# punto5sq.net
KiCad netlist of a schematic drawn in Altium Designer
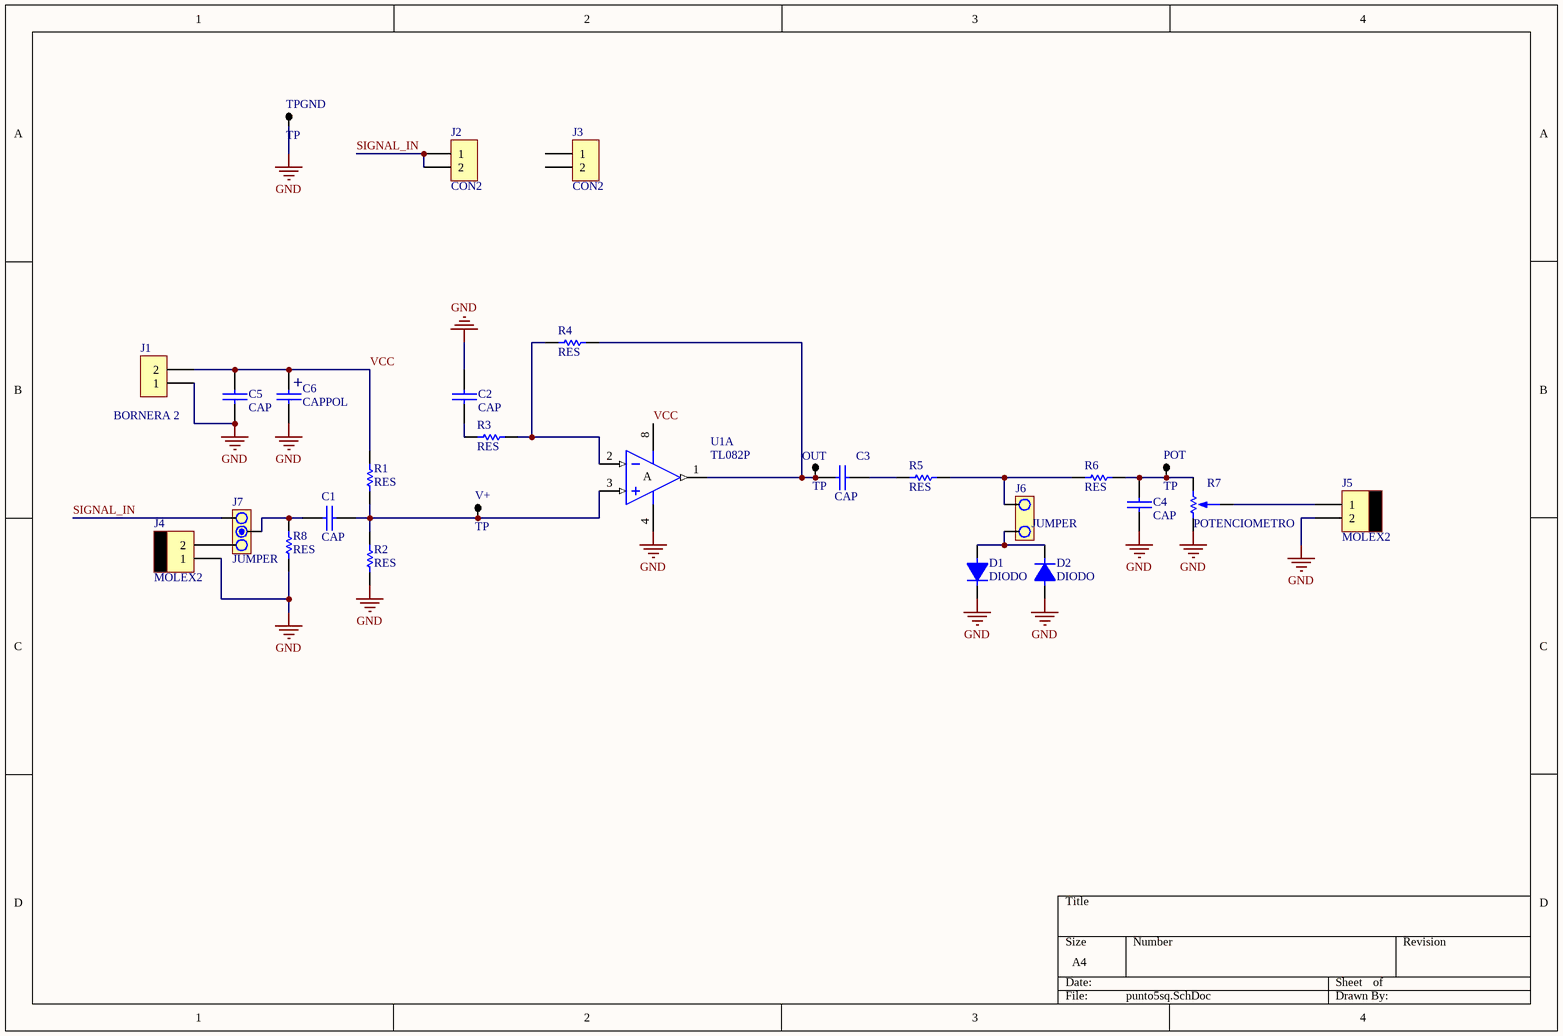
[diagram p0: punto5sq.SchDoc]

(export (version "E")
  (design (tool "Eeschema 10.0.6"))
  (components
    (comp (ref "C1") (value "CAP") (footprint "CAP200") (libsource (lib "LIBEBAL") (part "CAP")))
    (comp (ref "C2") (value "CAP") (footprint "CAP200") (libsource (lib "LIBEBAL") (part "CAP")))
    (comp (ref "C3") (value "CAP") (footprint "CAP200") (libsource (lib "LIBEBAL") (part "CAP")))
    (comp (ref "C4") (value "CAP") (footprint "CAP200") (libsource (lib "LIBEBAL") (part "CAP")))
    (comp (ref "C5") (value "CAP") (footprint "CAP200") (libsource (lib "LIBEBAL") (part "CAP")))
    (comp (ref "C6") (value "CAPPOL") (footprint "CAP100RP") (libsource (lib "LIBEBAL") (part "CAPPOL")))
    (comp (ref "D1") (value "DIODO") (footprint "DO41") (libsource (lib "LIBEBAL") (part "DIODO")))
    (comp (ref "D2") (value "DIODO") (footprint "DO41") (libsource (lib "LIBEBAL") (part "DIODO")))
    (comp (ref "J1")
      (value "BORNERA 2")
      (footprint "BORNERA2")
      (libsource (lib "LIBEBAL") (part "BORNERA 2"))
    )
    (comp (ref "J2") (value "CON2") (footprint "SIP2") (libsource (lib "LIBEBAL") (part "CON2")))
    (comp (ref "J3") (value "CON2") (footprint "SIP2") (libsource (lib "LIBEBAL") (part "CON2")))
    (comp (ref "J4") (value "MOLEX2") (footprint "MOLEX2") (libsource (lib "") (part "MOLEX2_1")))
    (comp (ref "J5") (value "MOLEX2") (footprint "MOLEX2") (libsource (lib "LIBEBAL") (part "MOLEX2")))
    (comp (ref "J6") (value "JUMPER") (footprint "JUMPER2") (libsource (lib "LIBEBAL") (part "JUMPER")))
    (comp (ref "J7") (value "JUMPER") (footprint "JUMPER3") (libsource (lib "LIBEBAL") (part "JUMPER3")))
    (comp (ref "OUT") (value "TP") (footprint "TPTH") (libsource (lib "LIBEBAL") (part "TP")))
    (comp (ref "POT") (value "TP") (footprint "TPTH") (libsource (lib "LIBEBAL") (part "TP")))
    (comp (ref "R1") (value "RES") (footprint "RES400") (libsource (lib "LIBEBAL") (part "RES")))
    (comp (ref "R2") (value "RES") (footprint "RES400") (libsource (lib "LIBEBAL") (part "RES")))
    (comp (ref "R3") (value "RES") (footprint "RES400") (libsource (lib "LIBEBAL") (part "RES")))
    (comp (ref "R4") (value "RES") (footprint "RES400") (libsource (lib "LIBEBAL") (part "RES")))
    (comp (ref "R5") (value "RES") (footprint "RES400") (libsource (lib "LIBEBAL") (part "RES")))
    (comp (ref "R6") (value "RES") (footprint "RES400") (libsource (lib "LIBEBAL") (part "RES")))
    (comp (ref "R7")
      (value "POTENCIOMETRO")
      (footprint "POTENCIOMETRO")
      (libsource (lib "LIBEBAL") (part "POTENCIOMETRO"))
    )
    (comp (ref "R8") (value "RES") (footprint "RES400") (libsource (lib "LIBEBAL") (part "RES")))
    (comp (ref "TPGND") (value "TP") (footprint "TPTH") (libsource (lib "LIBEBAL") (part "TP")))
    (comp (ref "U1")
      (value "TL082P")
      (footprint "P008")
      (description "JFET-Input Operational Amplifier")
      (fields (field (name "PUBLISHER") "Altium Limited"))
      (libsource (lib "TI Operational Amplifier") (part "TL082P"))
    )
    (comp (ref "V+") (value "TP") (footprint "TPTH") (libsource (lib "LIBEBAL") (part "TP")))
  )
  (nets
    (net (code "1") (name "/SIGNAL_IN") (class "Default")
      (node (ref "J2") (pin "1") (pinfunction "1_1") (pintype "passive"))
      (node (ref "J2") (pin "2") (pinfunction "2_2") (pintype "passive"))
      (node (ref "J7") (pin "3") (pinfunction "3_3") (pintype "passive"))
    )
    (net (code "2") (name "/VCC") (class "Default")
      (node (ref "C5") (pin "1") (pinfunction "1_1") (pintype "passive"))
      (node (ref "C6") (pin "1") (pinfunction "1_1") (pintype "passive"))
      (node (ref "J1") (pin "2") (pinfunction "2_2") (pintype "passive"))
      (node (ref "R1") (pin "2") (pinfunction "2_2") (pintype "passive"))
      (node (ref "U1") (pin "8") (pinfunction "V+_8") (pintype "power_in"))
    )
    (net (code "3") (name "GND") (class "Default")
      (node (ref "C2") (pin "2") (pinfunction "2_2") (pintype "passive"))
      (node (ref "C4") (pin "2") (pinfunction "2_2") (pintype "passive"))
      (node (ref "C5") (pin "2") (pinfunction "2_2") (pintype "passive"))
      (node (ref "C6") (pin "2") (pinfunction "2_2") (pintype "passive"))
      (node (ref "D1") (pin "2") (pinfunction "2_2") (pintype "passive"))
      (node (ref "D2") (pin "1") (pinfunction "1_1") (pintype "passive"))
      (node (ref "J1") (pin "1") (pinfunction "1_1") (pintype "passive"))
      (node (ref "J4") (pin "1") (pinfunction "1_1") (pintype "passive"))
      (node (ref "J5") (pin "2") (pinfunction "2_2") (pintype "passive"))
      (node (ref "R2") (pin "1") (pinfunction "1_1") (pintype "passive"))
      (node (ref "R7") (pin "3") (pinfunction "3_3") (pintype "passive"))
      (node (ref "R8") (pin "2") (pinfunction "2_2") (pintype "passive"))
      (node (ref "TPGND") (pin "1") (pinfunction "1_1") (pintype "passive"))
      (node (ref "U1") (pin "4") (pinfunction "V-_4") (pintype "power_in"))
    )
    (net (code "4") (name "Net-(C1-Pad2)") (class "Default")
      (node (ref "C1") (pin "2") (pinfunction "2_2") (pintype "passive"))
      (node (ref "J7") (pin "2") (pinfunction "2_2") (pintype "passive"))
      (node (ref "R8") (pin "1") (pinfunction "1_1") (pintype "passive"))
    )
    (net (code "5") (name "Net-(C2-Pad1)") (class "Default")
      (node (ref "C2") (pin "1") (pinfunction "1_1") (pintype "passive"))
      (node (ref "R3") (pin "1") (pinfunction "1_1") (pintype "passive"))
    )
    (net (code "6") (name "Net-(C3-Pad2)") (class "Default")
      (node (ref "C3") (pin "2") (pinfunction "2_2") (pintype "passive"))
      (node (ref "R5") (pin "1") (pinfunction "1_1") (pintype "passive"))
    )
    (net (code "7") (name "Net-(C4-Pad1)") (class "Default")
      (node (ref "C4") (pin "1") (pinfunction "1_1") (pintype "passive"))
      (node (ref "POT") (pin "1") (pinfunction "1_1") (pintype "passive"))
      (node (ref "R6") (pin "2") (pinfunction "2_2") (pintype "passive"))
      (node (ref "R7") (pin "1") (pinfunction "1_1") (pintype "passive"))
    )
    (net (code "8") (name "Net-(D1-Pad1)") (class "Default")
      (node (ref "D1") (pin "1") (pinfunction "1_1") (pintype "passive"))
      (node (ref "D2") (pin "2") (pinfunction "2_2") (pintype "passive"))
      (node (ref "J6") (pin "1") (pinfunction "1_1") (pintype "passive"))
    )
    (net (code "9") (name "Net-(J4-Pad2)") (class "Default")
      (node (ref "J4") (pin "2") (pinfunction "2_2") (pintype "passive"))
      (node (ref "J7") (pin "1") (pinfunction "1_1") (pintype "passive"))
    )
    (net (code "10") (name "Net-(J5-Pad1)") (class "Default")
      (node (ref "J5") (pin "1") (pinfunction "1_1") (pintype "passive"))
      (node (ref "R7") (pin "2") (pinfunction "2_2") (pintype "passive"))
    )
    (net (code "11") (name "Net-(J6-Pad2)") (class "Default")
      (node (ref "J6") (pin "2") (pinfunction "2_2") (pintype "passive"))
      (node (ref "R5") (pin "2") (pinfunction "2_2") (pintype "passive"))
      (node (ref "R6") (pin "1") (pinfunction "1_1") (pintype "passive"))
    )
    (net (code "12") (name "Net-(U1A-IN+)") (class "Default")
      (node (ref "C1") (pin "1") (pinfunction "1_1") (pintype "passive"))
      (node (ref "R1") (pin "1") (pinfunction "1_1") (pintype "passive"))
      (node (ref "R2") (pin "2") (pinfunction "2_2") (pintype "passive"))
      (node (ref "U1") (pin "3") (pinfunction "IN+_3") (pintype "input"))
      (node (ref "V+") (pin "1") (pinfunction "1_1") (pintype "passive"))
    )
    (net (code "13") (name "Net-(U1A-IN-)") (class "Default")
      (node (ref "R3") (pin "2") (pinfunction "2_2") (pintype "passive"))
      (node (ref "R4") (pin "1") (pinfunction "1_1") (pintype "passive"))
      (node (ref "U1") (pin "2") (pinfunction "IN-_2") (pintype "input"))
    )
    (net (code "14") (name "Net-(U1A-OUT)") (class "Default")
      (node (ref "C3") (pin "1") (pinfunction "1_1") (pintype "passive"))
      (node (ref "OUT") (pin "1") (pinfunction "1_1") (pintype "passive"))
      (node (ref "R4") (pin "2") (pinfunction "2_2") (pintype "passive"))
      (node (ref "U1") (pin "1") (pinfunction "OUT_1") (pintype "output"))
    )
    (net (code "15") (name "unconnected-(J3-Pad1)") (class "Default")
      (node (ref "J3") (pin "1") (pinfunction "1_1") (pintype "passive"))
    )
    (net (code "16") (name "unconnected-(J3-Pad2)") (class "Default")
      (node (ref "J3") (pin "2") (pinfunction "2_2") (pintype "passive"))
    )
  )
)
